# S7G7_footprint_simplified_w_ethernet_v1p.net
KiCad netlist of a schematic drawn in EAGLE
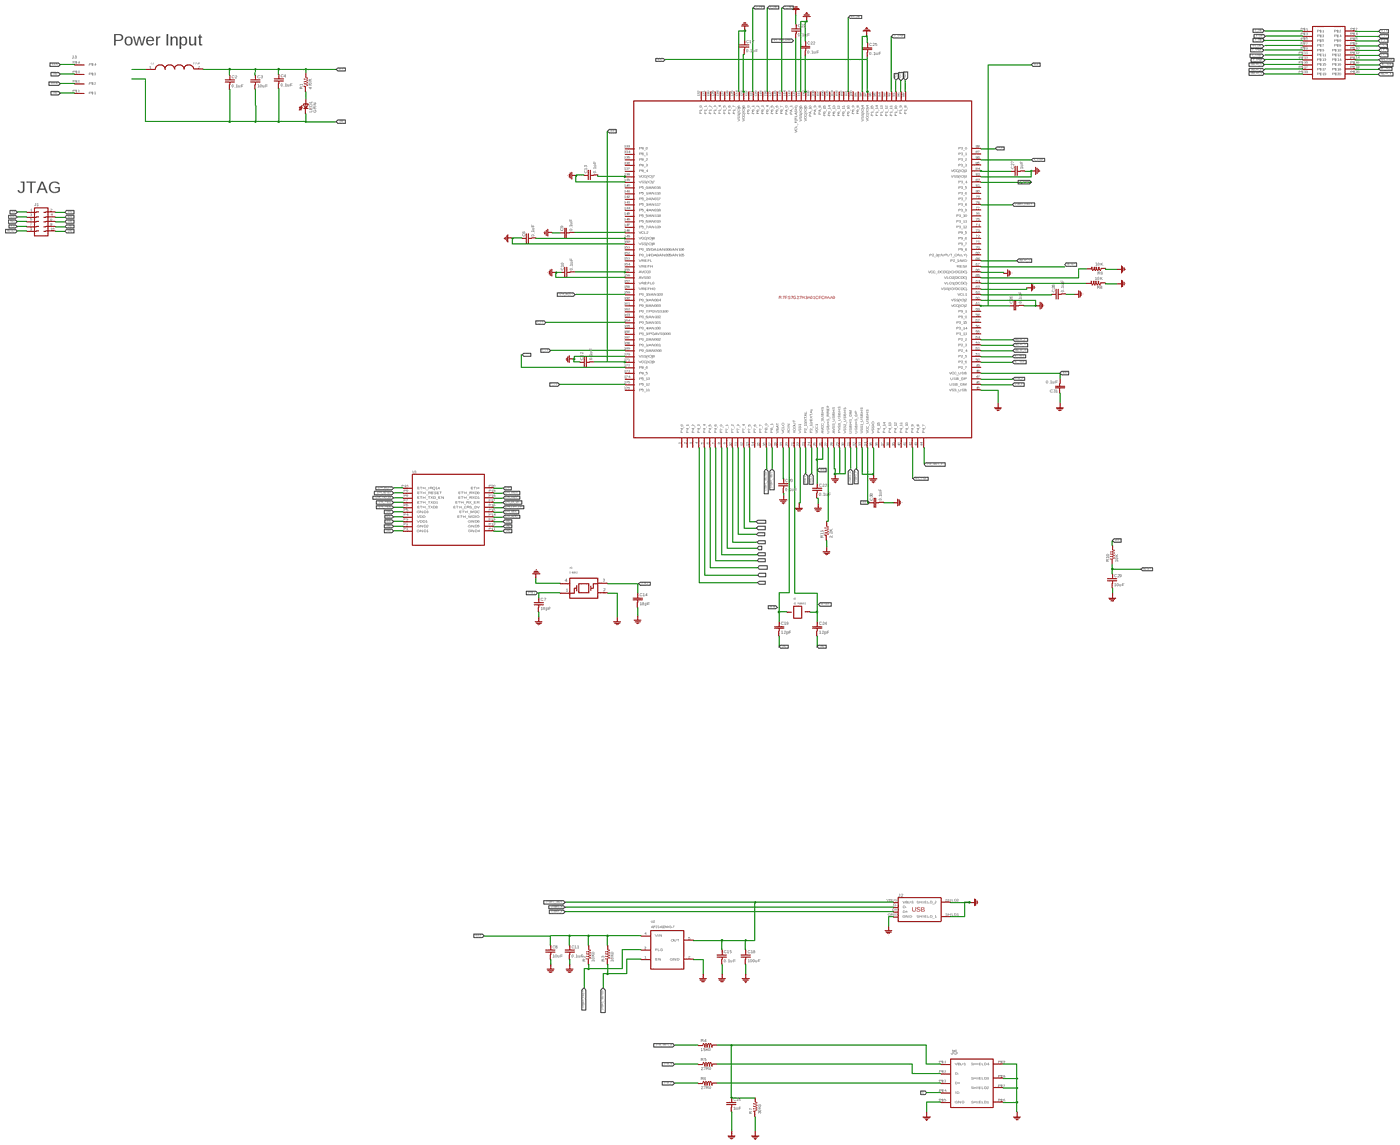
[diagram p0: schematic, sheet 1, overview]
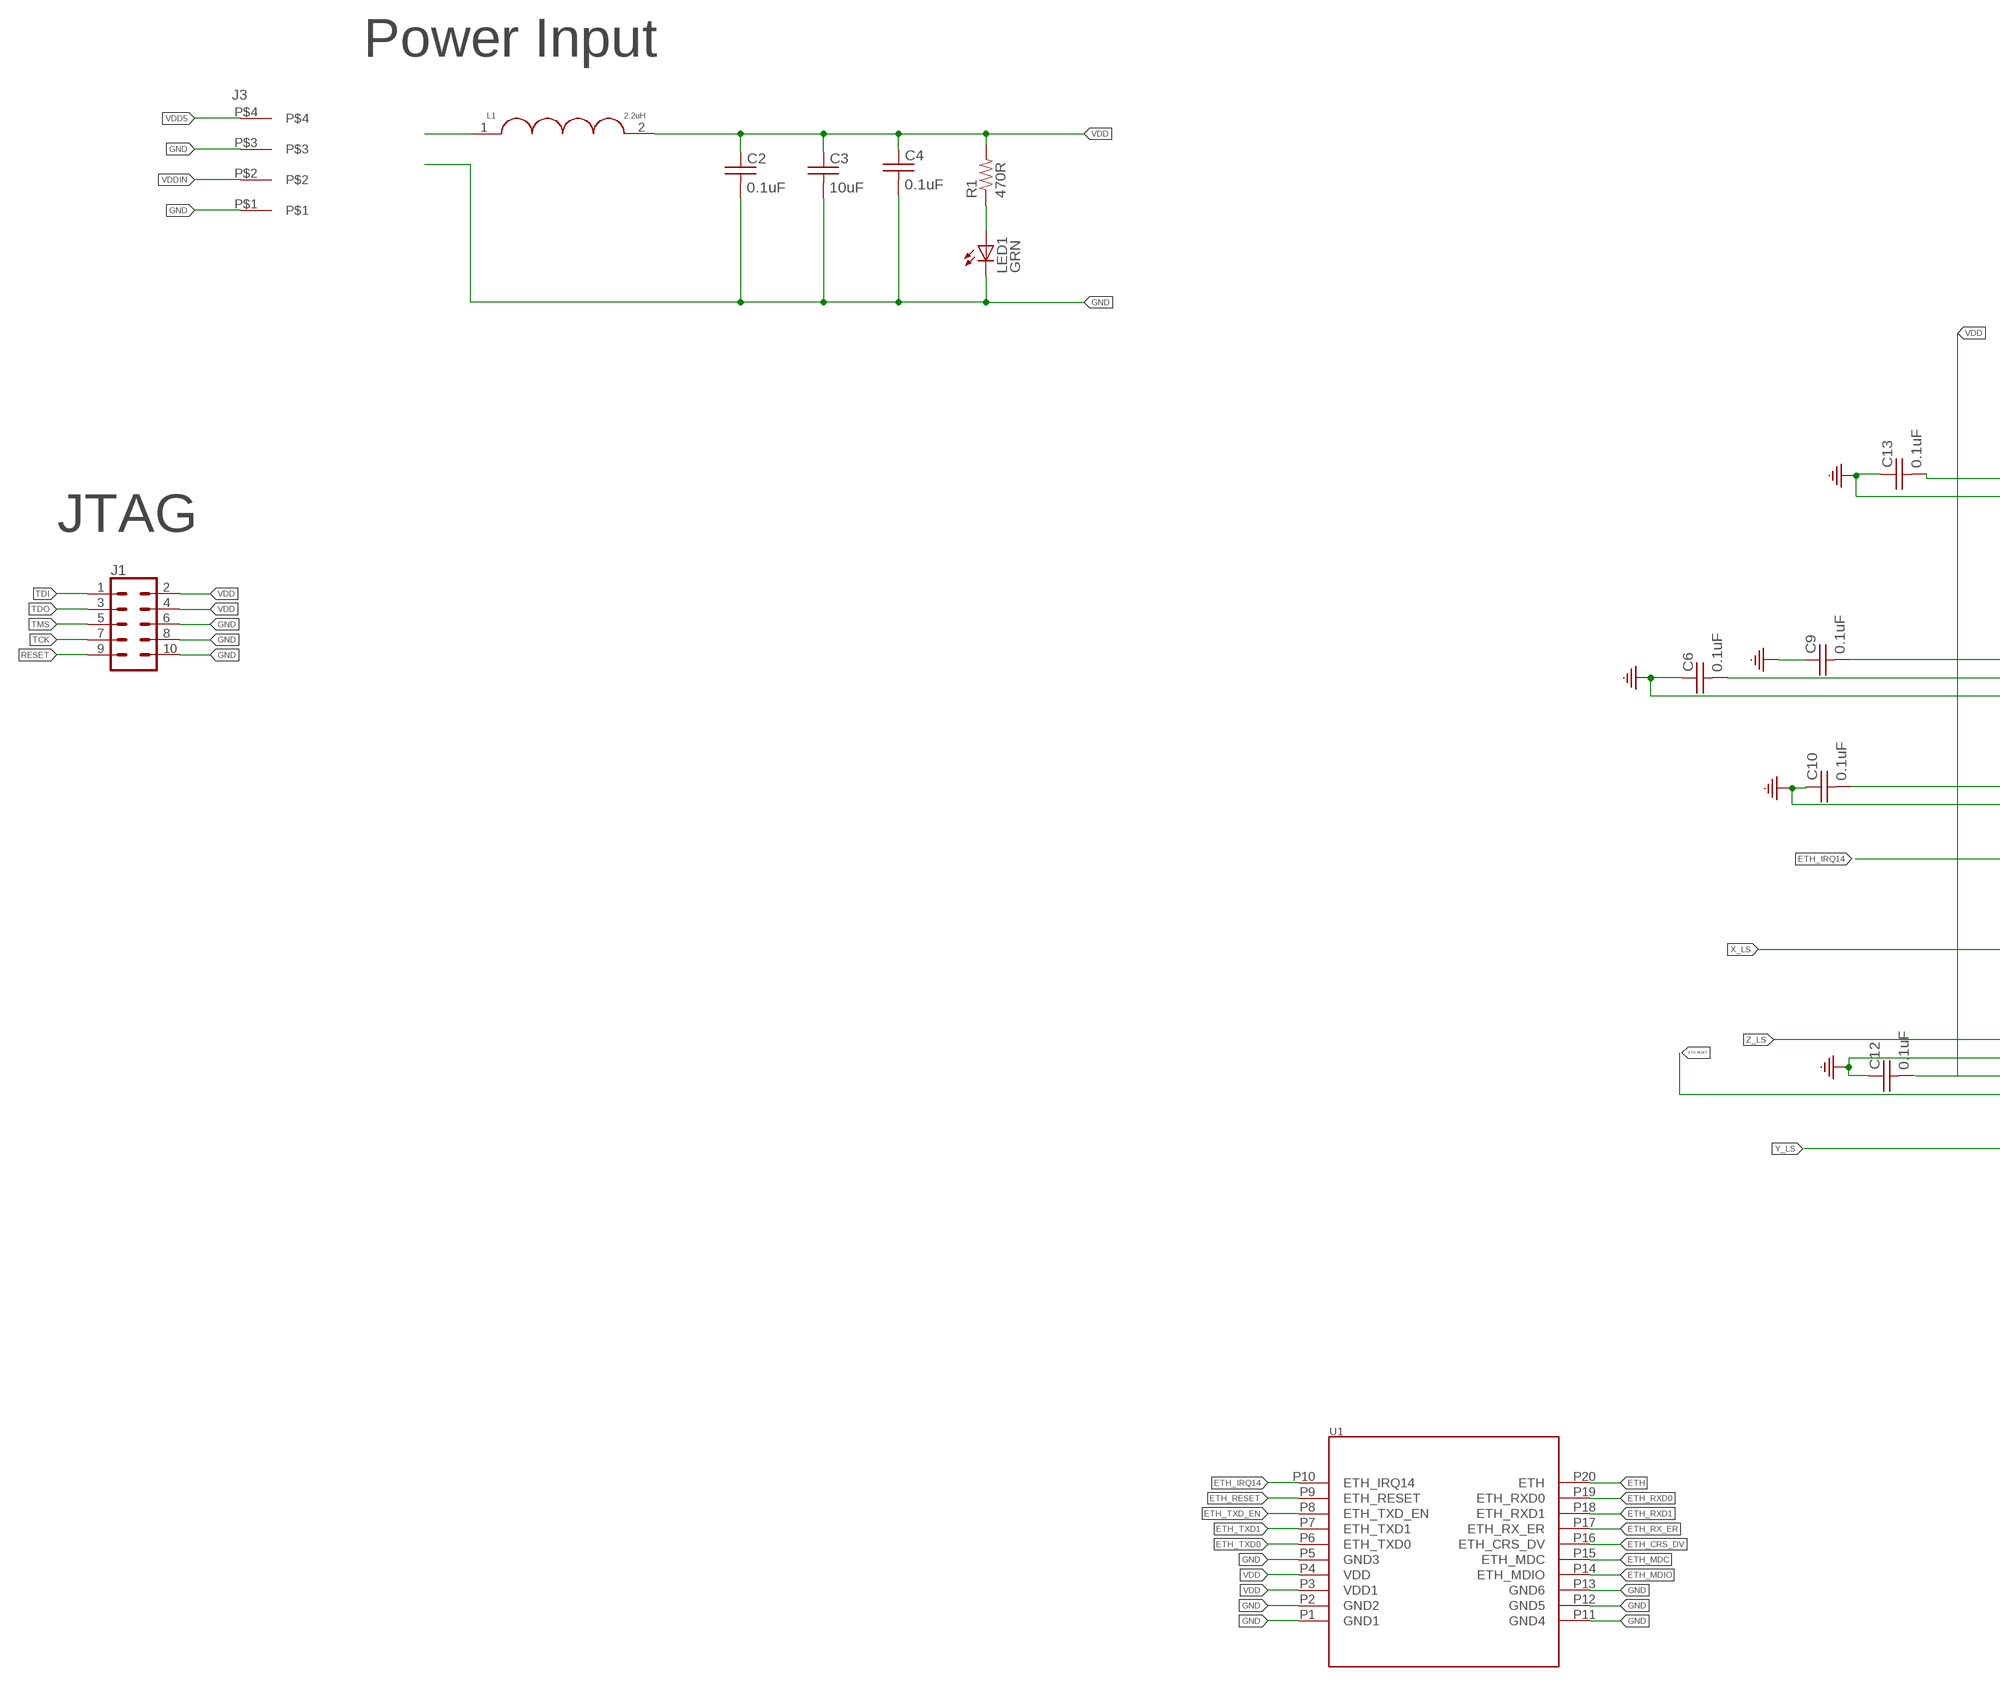
[diagram p1: schematic, sheet 1, part 1 of 4]
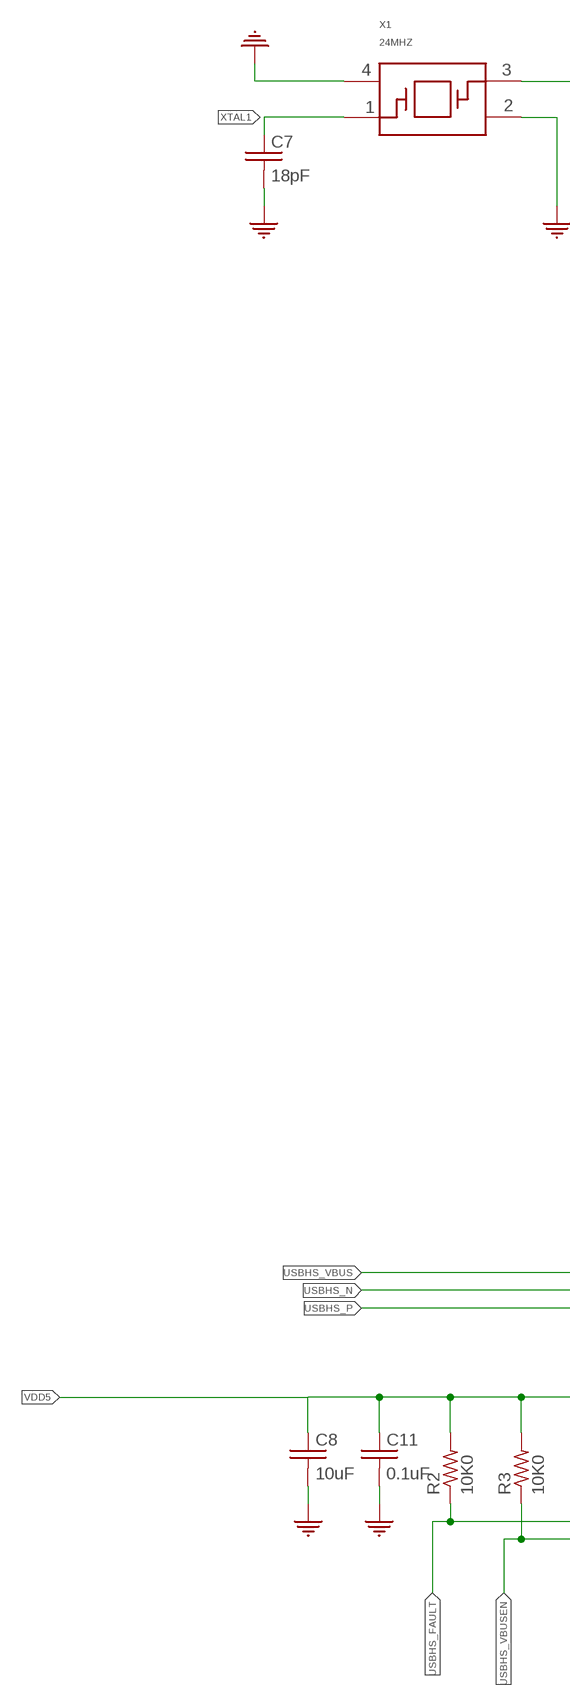
[diagram p2: schematic, sheet 1, part 2 of 4]
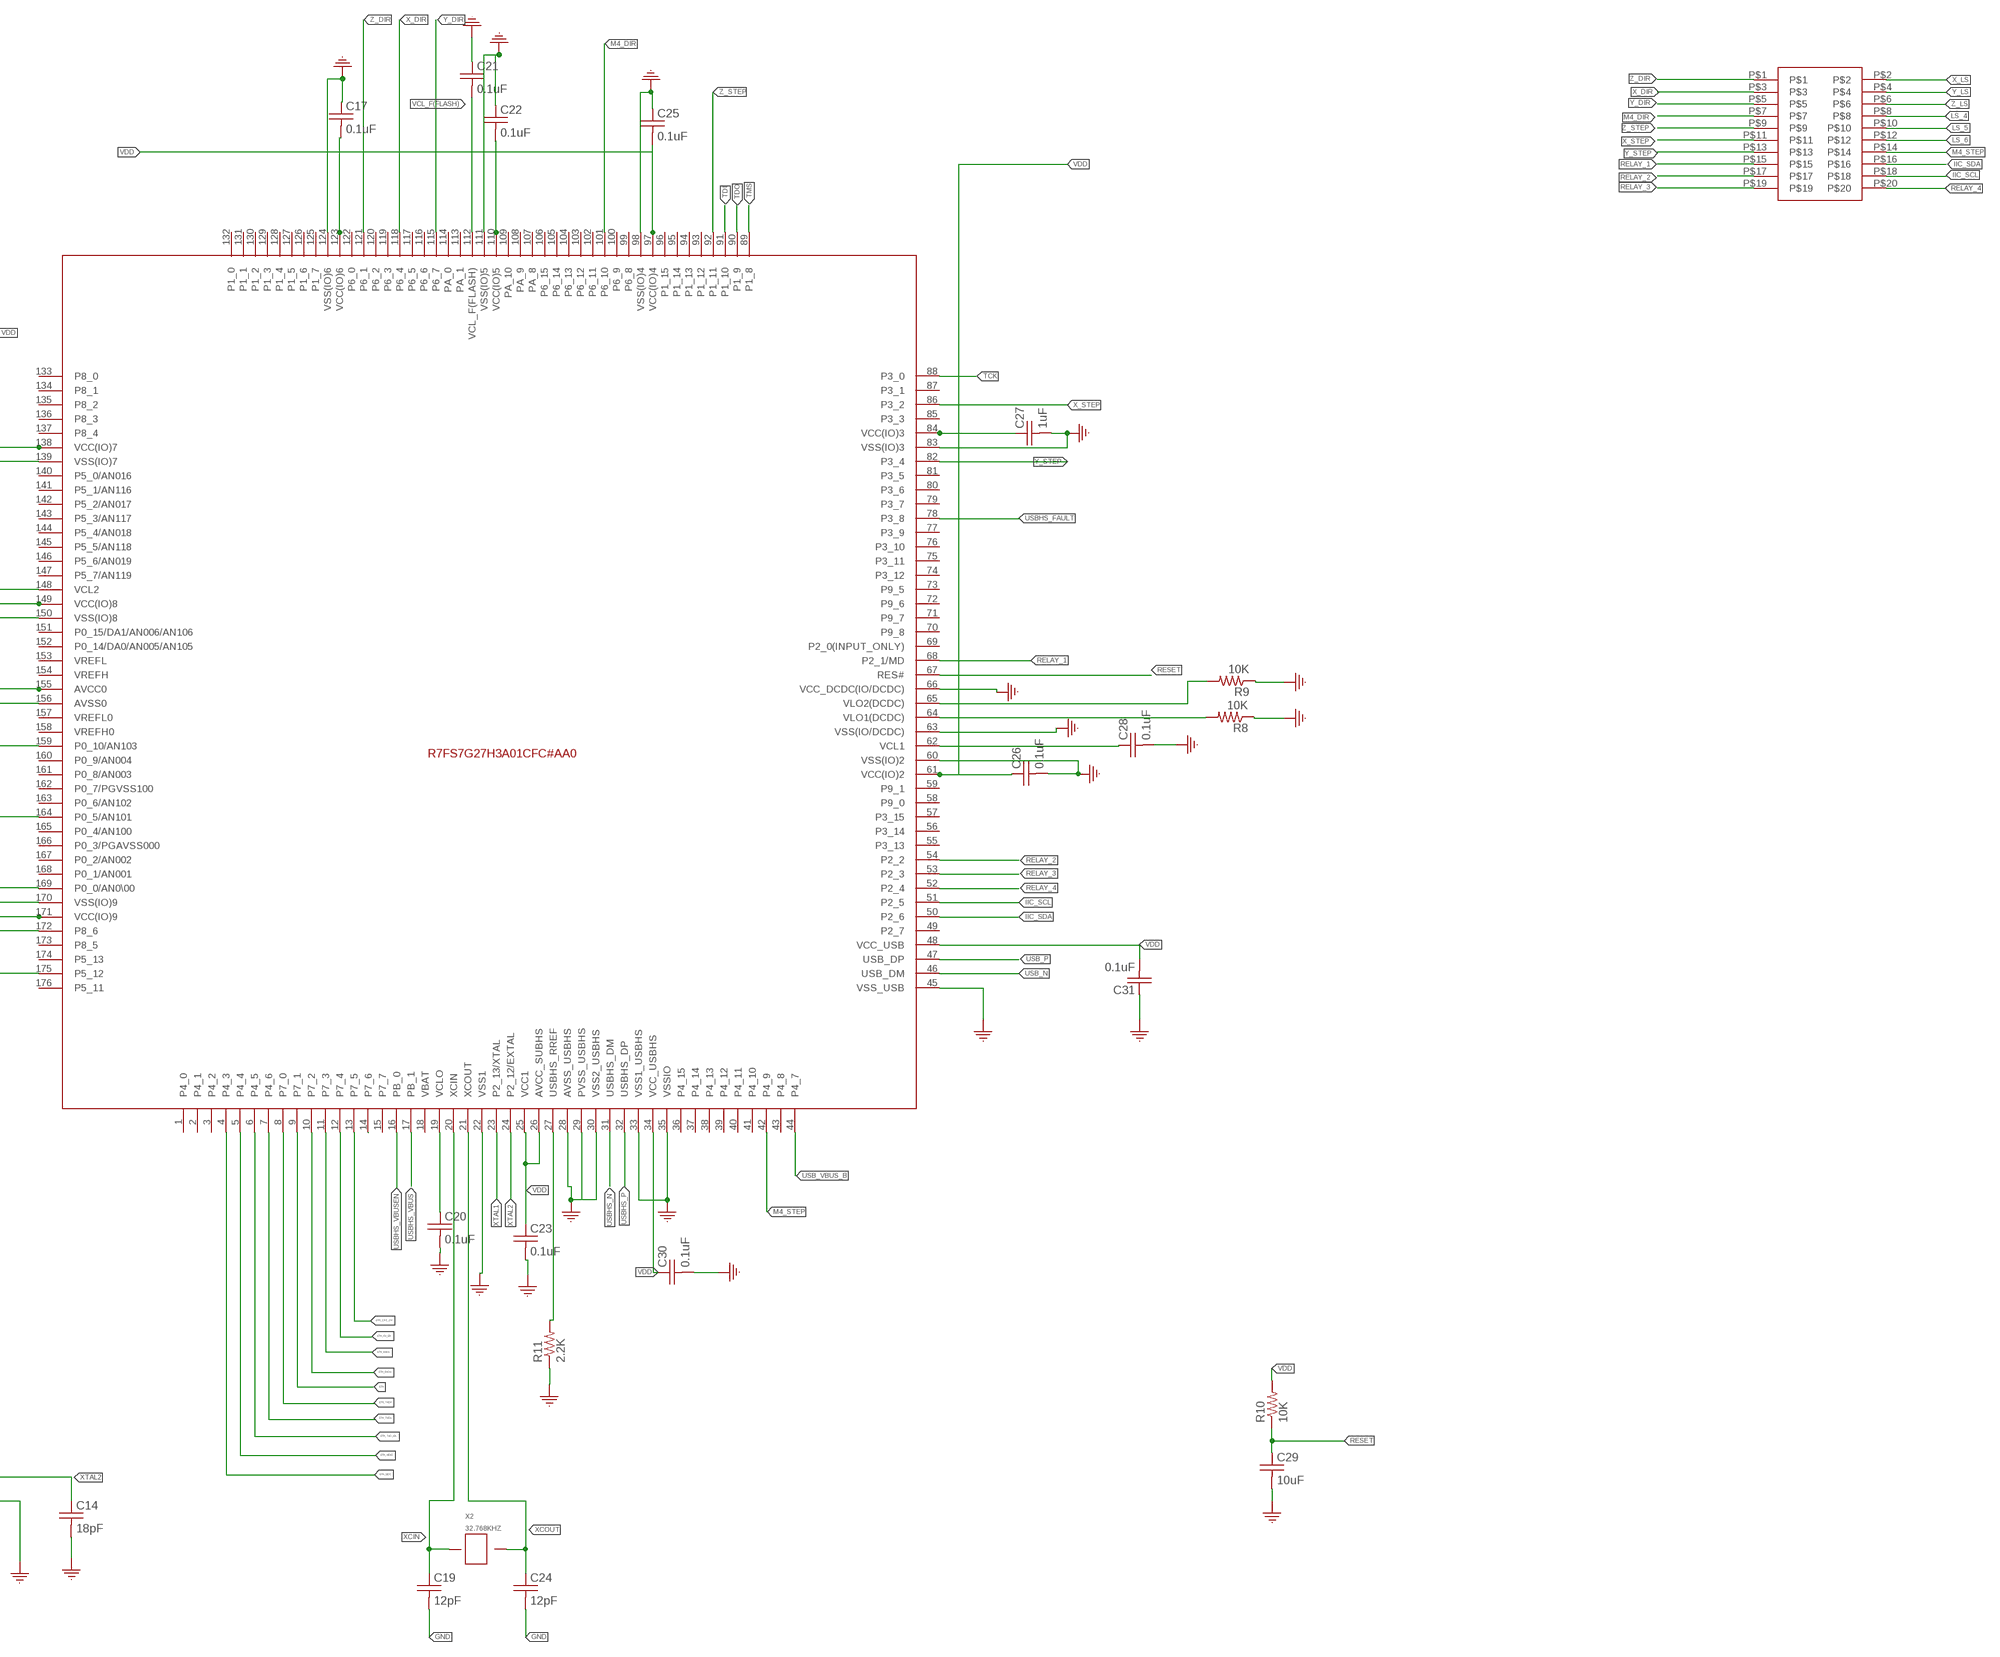
[diagram p3: schematic, sheet 1, part 3 of 4]
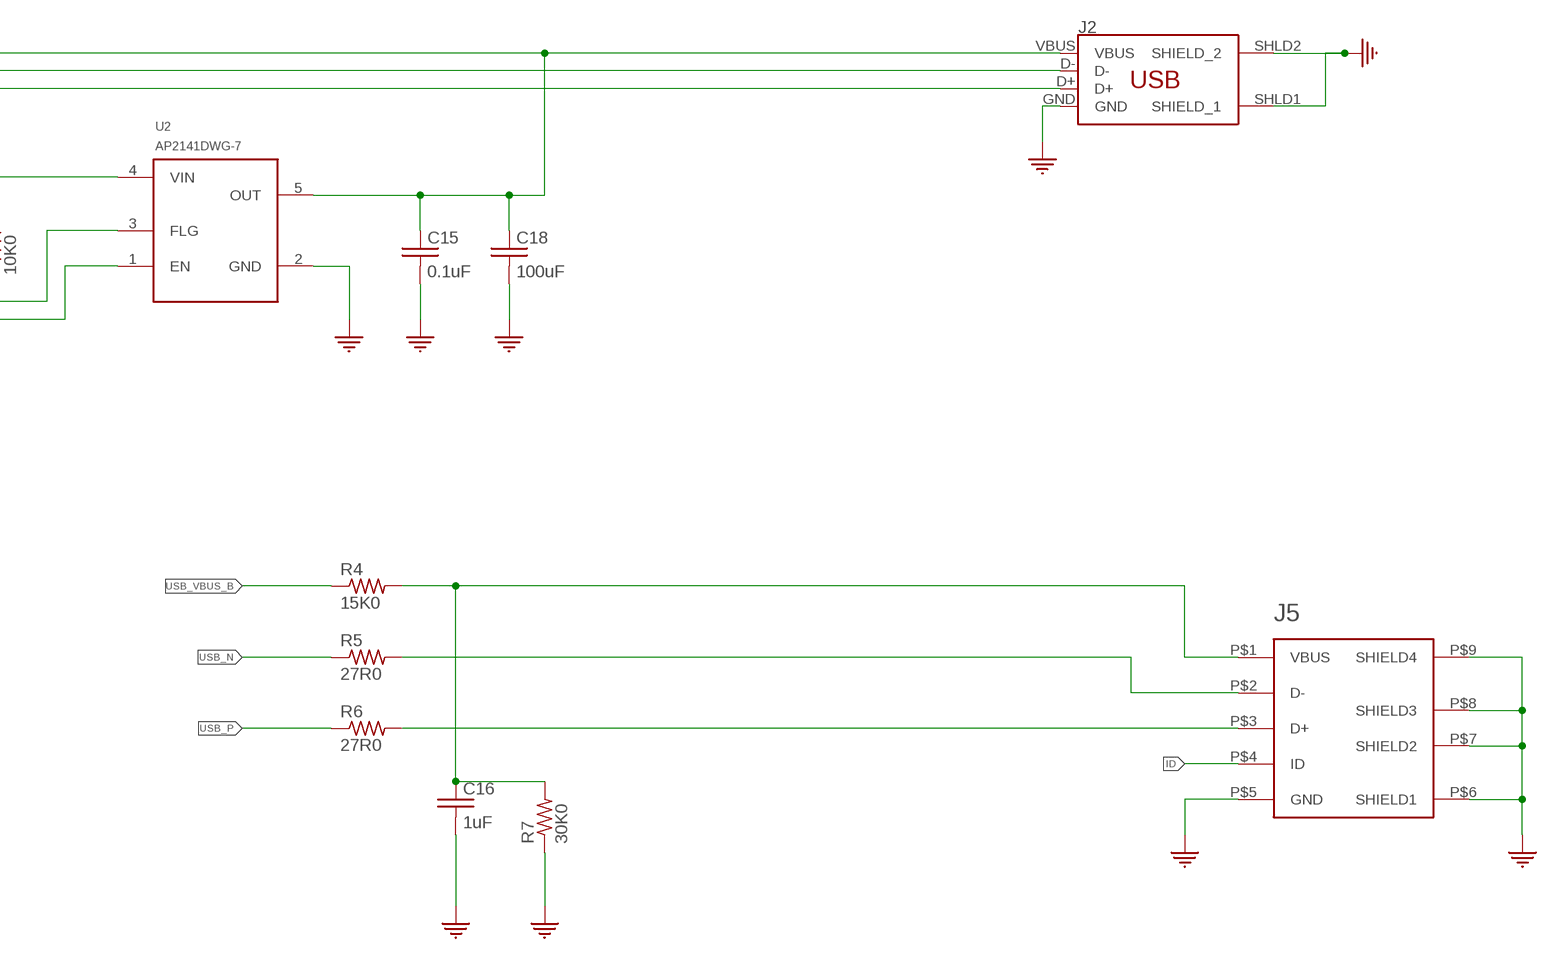
[diagram p4: schematic, sheet 1, part 4 of 4]

(export (version "E")
  (design (tool "Eeschema 10.0.6"))
  (components
    (comp (ref "C2")
      (value "0.1uF")
      (footprint "eagle-import:0402")
      (libsource (lib "eagle-import") (part "C_0402"))
    )
    (comp (ref "C3")
      (value "10uF")
      (footprint "eagle-import:0402")
      (libsource (lib "eagle-import") (part "C_0402"))
    )
    (comp (ref "C4")
      (value "0.1uF")
      (footprint "eagle-import:0402")
      (libsource (lib "eagle-import") (part "C_0402"))
    )
    (comp (ref "C6")
      (value "0.1uF")
      (footprint "eagle-import:0402")
      (libsource (lib "eagle-import") (part "C_0402"))
    )
    (comp (ref "C7")
      (value "18pF")
      (footprint "eagle-import:0402")
      (libsource (lib "eagle-import") (part "C_0402"))
    )
    (comp (ref "C8")
      (value "10uF")
      (footprint "eagle-import:0402")
      (libsource (lib "eagle-import") (part "C_0402"))
    )
    (comp (ref "C9")
      (value "0.1uF")
      (footprint "eagle-import:0402")
      (libsource (lib "eagle-import") (part "C_0402"))
    )
    (comp (ref "C10")
      (value "0.1uF")
      (footprint "eagle-import:0402")
      (libsource (lib "eagle-import") (part "C_0402"))
    )
    (comp (ref "C11")
      (value "0.1uF")
      (footprint "eagle-import:0402")
      (libsource (lib "eagle-import") (part "C_0402"))
    )
    (comp (ref "C12")
      (value "0.1uF")
      (footprint "eagle-import:0402")
      (libsource (lib "eagle-import") (part "C_0402"))
    )
    (comp (ref "C13")
      (value "0.1uF")
      (footprint "eagle-import:0402")
      (libsource (lib "eagle-import") (part "C_0402"))
    )
    (comp (ref "C14")
      (value "18pF")
      (footprint "eagle-import:0402")
      (libsource (lib "eagle-import") (part "C_0402"))
    )
    (comp (ref "C15")
      (value "0.1uF")
      (footprint "eagle-import:0402")
      (libsource (lib "eagle-import") (part "C_0402"))
    )
    (comp (ref "C16")
      (value "1uF")
      (footprint "eagle-import:0402")
      (libsource (lib "eagle-import") (part "C_0402"))
    )
    (comp (ref "C17")
      (value "0.1uF")
      (footprint "eagle-import:0402")
      (libsource (lib "eagle-import") (part "C_0402"))
    )
    (comp (ref "C18")
      (value "100uF")
      (footprint "eagle-import:C1210")
      (libsource (lib "eagle-import") (part "C_1210"))
    )
    (comp (ref "C19")
      (value "12pF")
      (footprint "eagle-import:0402")
      (libsource (lib "eagle-import") (part "C_0402"))
    )
    (comp (ref "C20")
      (value "0.1uF")
      (footprint "eagle-import:0402")
      (libsource (lib "eagle-import") (part "C_0402"))
    )
    (comp (ref "C21")
      (value "0.1uF")
      (footprint "eagle-import:0402")
      (libsource (lib "eagle-import") (part "C_0402"))
    )
    (comp (ref "C22")
      (value "0.1uF")
      (footprint "eagle-import:0402")
      (libsource (lib "eagle-import") (part "C_0402"))
    )
    (comp (ref "C23")
      (value "0.1uF")
      (footprint "eagle-import:0402")
      (libsource (lib "eagle-import") (part "C_0402"))
    )
    (comp (ref "C24")
      (value "12pF")
      (footprint "eagle-import:0402")
      (libsource (lib "eagle-import") (part "C_0402"))
    )
    (comp (ref "C25")
      (value "0.1uF")
      (footprint "eagle-import:0402")
      (libsource (lib "eagle-import") (part "C_0402"))
    )
    (comp (ref "C26")
      (value "0.1uF")
      (footprint "eagle-import:0402")
      (libsource (lib "eagle-import") (part "C_0402"))
    )
    (comp (ref "C27")
      (value "1uF")
      (footprint "eagle-import:0402")
      (libsource (lib "eagle-import") (part "C_0402"))
    )
    (comp (ref "C28")
      (value "0.1uF")
      (footprint "eagle-import:0402")
      (libsource (lib "eagle-import") (part "C_0402"))
    )
    (comp (ref "C29")
      (value "10uF")
      (footprint "eagle-import:0402")
      (libsource (lib "eagle-import") (part "C_0402"))
    )
    (comp (ref "C30")
      (value "0.1uF")
      (footprint "eagle-import:0402")
      (libsource (lib "eagle-import") (part "C_0402"))
    )
    (comp (ref "C31")
      (value "0.1uF")
      (footprint "eagle-import:0402")
      (libsource (lib "eagle-import") (part "C_0402"))
    )
    (comp (ref "J1")
      (value "CONN_05X2PTH")
      (footprint "eagle-import:2X5")
      (libsource (lib "eagle-import") (part "CONN_05X2PTH"))
    )
    (comp (ref "J2")
      (value "USB_A")
      (footprint "eagle-import:USB_A_SMT")
      (libsource (lib "eagle-import") (part "USB_A"))
    )
    (comp (ref "J3")
      (value "3.81MM_1_X_4_RT_ANGLE_PLUG_HEADER")
      (footprint "eagle-import:1X4_3.81MM_PITCH")
      (libsource (lib "eagle-import") (part "3.81MM_1_X_4_RT_ANGLE_PLUG_HEADER"))
    )
    (comp (ref "J4")
      (value "2_X_10_HEADER_GENERIC")
      (footprint "eagle-import:2_X_10_.1_INCH")
      (libsource (lib "eagle-import") (part "2_X_10_HEADER_GENERIC"))
    )
    (comp (ref "J5")
      (value "USB_MICRO-B")
      (footprint "eagle-import:USB_MICRO-B")
      (libsource (lib "eagle-import") (part "USB_MICRO-B"))
    )
    (comp (ref "L1")
      (value "2.2uH")
      (footprint "eagle-import:1008_(2520_METRIC)")
      (libsource (lib "eagle-import") (part "INDUCTOR_1008_2.2_MH_1.3A"))
    )
    (comp (ref "LED1")
      (value "LED_0805_GREEN")
      (footprint "eagle-import:LED_0805_GREEN")
      (libsource (lib "eagle-import") (part "LED_0805_GREEN"))
    )
    (comp (ref "R1")
      (value "470R")
      (footprint "eagle-import:0402")
      (libsource (lib "eagle-import") (part "R_0402"))
    )
    (comp (ref "R2")
      (value "10K0")
      (footprint "eagle-import:0402")
      (libsource (lib "eagle-import") (part "R_0402"))
    )
    (comp (ref "R3")
      (value "10K0")
      (footprint "eagle-import:0402")
      (libsource (lib "eagle-import") (part "R_0402"))
    )
    (comp (ref "R4")
      (value "15K0")
      (footprint "eagle-import:0402")
      (libsource (lib "eagle-import") (part "R_0402"))
    )
    (comp (ref "R5")
      (value "27R0")
      (footprint "eagle-import:0402")
      (libsource (lib "eagle-import") (part "R_0402"))
    )
    (comp (ref "R6")
      (value "27R0")
      (footprint "eagle-import:0402")
      (libsource (lib "eagle-import") (part "R_0402"))
    )
    (comp (ref "R7")
      (value "30K0")
      (footprint "eagle-import:0402")
      (libsource (lib "eagle-import") (part "R_0402"))
    )
    (comp (ref "R8")
      (value "10K")
      (footprint "eagle-import:0402")
      (libsource (lib "eagle-import") (part "R_0402"))
    )
    (comp (ref "R9")
      (value "10K")
      (footprint "eagle-import:0402")
      (libsource (lib "eagle-import") (part "R_0402"))
    )
    (comp (ref "R10")
      (value "10K")
      (footprint "eagle-import:0402")
      (libsource (lib "eagle-import") (part "R_0402"))
    )
    (comp (ref "R11")
      (value "2.2K")
      (footprint "eagle-import:0402")
      (libsource (lib "eagle-import") (part "R_0402"))
    )
    (comp (ref "U1")
      (value "ETHERNET_HAT")
      (footprint "eagle-import:ETHERNET_HAT")
      (libsource (lib "eagle-import") (part "ETHERNET_HAT"))
    )
    (comp (ref "U2")
      (value "AP2141DWG-5")
      (footprint "eagle-import:SOT-23-5")
      (libsource (lib "eagle-import") (part "AP2141DWG-5"))
    )
    (comp (ref "U5")
      (value "S7G2_X_176")
      (footprint "eagle-import:LQFP176_24X24")
      (libsource (lib "eagle-import") (part "S7G2_X_176"))
    )
    (comp (ref "X1")
      (value "24MHZ")
      (footprint "eagle-import:SMD_3225")
      (libsource (lib "eagle-import") (part "XTAL_24_MHZ"))
    )
    (comp (ref "X2")
      (value "32.768KHZ")
      (footprint "eagle-import:SMD_X_2_PADS")
      (libsource (lib "eagle-import") (part "XTAL_32.768KHZ"))
    )
  )
  (nets
    (net (code "1") (name "ETH") (class "Default")
      (node (ref "U1") (pin "P20") (pinfunction "ETH_P20") (pintype "bidirectional"))
      (node (ref "U5") (pin "9") (pinfunction "P7_1_9") (pintype "bidirectional"))
    )
    (net (code "2") (name "ETH_CRS_DV") (class "Default")
      (node (ref "U1") (pin "P16") (pinfunction "ETH_CRS_DV_P16") (pintype "bidirectional"))
      (node (ref "U5") (pin "13") (pinfunction "P7_5_13") (pintype "bidirectional"))
    )
    (net (code "3") (name "ETH_IRQ14") (class "Default")
      (node (ref "U1") (pin "P10") (pinfunction "ETH_IRQ14_P10") (pintype "bidirectional"))
      (node (ref "U5") (pin "159") (pinfunction "P0_10/AN103_159") (pintype "bidirectional"))
    )
    (net (code "4") (name "ETH_MDC") (class "Default")
      (node (ref "U1") (pin "P15") (pinfunction "ETH_MDC_P15") (pintype "bidirectional"))
      (node (ref "U5") (pin "4") (pinfunction "P4_3_4") (pintype "bidirectional"))
    )
    (net (code "5") (name "ETH_MDIO") (class "Default")
      (node (ref "U1") (pin "P14") (pinfunction "ETH_MDIO_P14") (pintype "bidirectional"))
      (node (ref "U5") (pin "5") (pinfunction "P4_4_5") (pintype "bidirectional"))
    )
    (net (code "6") (name "ETH_RESET") (class "Default")
      (node (ref "U1") (pin "P9") (pinfunction "ETH_RESET_P9") (pintype "bidirectional"))
      (node (ref "U5") (pin "172") (pinfunction "P8_6_172") (pintype "bidirectional"))
    )
    (net (code "7") (name "ETH_RXD0") (class "Default")
      (node (ref "U1") (pin "P19") (pinfunction "ETH_RXD0_P19") (pintype "bidirectional"))
      (node (ref "U5") (pin "10") (pinfunction "P7_2_10") (pintype "bidirectional"))
    )
    (net (code "8") (name "ETH_RXD1") (class "Default")
      (node (ref "U1") (pin "P18") (pinfunction "ETH_RXD1_P18") (pintype "bidirectional"))
      (node (ref "U5") (pin "11") (pinfunction "P7_3_11") (pintype "bidirectional"))
    )
    (net (code "9") (name "ETH_RX_ER") (class "Default")
      (node (ref "U1") (pin "P17") (pinfunction "ETH_RX_ER_P17") (pintype "bidirectional"))
      (node (ref "U5") (pin "12") (pinfunction "P7_4_12") (pintype "bidirectional"))
    )
    (net (code "10") (name "ETH_TXD0") (class "Default")
      (node (ref "U1") (pin "P6") (pinfunction "ETH_TXD0_P6") (pintype "bidirectional"))
      (node (ref "U5") (pin "8") (pinfunction "P7_0_8") (pintype "bidirectional"))
    )
    (net (code "11") (name "ETH_TXD1") (class "Default")
      (node (ref "U1") (pin "P7") (pinfunction "ETH_TXD1_P7") (pintype "bidirectional"))
      (node (ref "U5") (pin "7") (pinfunction "P4_6_7") (pintype "bidirectional"))
    )
    (net (code "12") (name "ETH_TXD_EN") (class "Default")
      (node (ref "U1") (pin "P8") (pinfunction "ETH_TXD_EN_P8") (pintype "bidirectional"))
      (node (ref "U5") (pin "6") (pinfunction "P4_5_6") (pintype "bidirectional"))
    )
    (net (code "13") (name "GND") (class "Default")
      (node (ref "C10") (pin "P$1") (pinfunction "1_P$1") (pintype "passive"))
      (node (ref "C11") (pin "P$2") (pinfunction "2_P$2") (pintype "passive"))
      (node (ref "C12") (pin "P$1") (pinfunction "1_P$1") (pintype "passive"))
      (node (ref "C13") (pin "P$1") (pinfunction "1_P$1") (pintype "passive"))
      (node (ref "C14") (pin "P$2") (pinfunction "2_P$2") (pintype "passive"))
      (node (ref "C15") (pin "P$2") (pinfunction "2_P$2") (pintype "passive"))
      (node (ref "C16") (pin "P$2") (pinfunction "2_P$2") (pintype "passive"))
      (node (ref "C17") (pin "P$1") (pinfunction "1_P$1") (pintype "passive"))
      (node (ref "C18") (pin "2") (pinfunction "2_2") (pintype "passive"))
      (node (ref "C19") (pin "P$2") (pinfunction "2_P$2") (pintype "passive"))
      (node (ref "C2") (pin "P$2") (pinfunction "2_P$2") (pintype "passive"))
      (node (ref "C20") (pin "P$2") (pinfunction "2_P$2") (pintype "passive"))
      (node (ref "C21") (pin "P$1") (pinfunction "1_P$1") (pintype "passive"))
      (node (ref "C22") (pin "P$1") (pinfunction "1_P$1") (pintype "passive"))
      (node (ref "C23") (pin "P$2") (pinfunction "2_P$2") (pintype "passive"))
      (node (ref "C24") (pin "P$2") (pinfunction "2_P$2") (pintype "passive"))
      (node (ref "C25") (pin "P$1") (pinfunction "1_P$1") (pintype "passive"))
      (node (ref "C26") (pin "P$2") (pinfunction "2_P$2") (pintype "passive"))
      (node (ref "C27") (pin "P$2") (pinfunction "2_P$2") (pintype "passive"))
      (node (ref "C28") (pin "P$2") (pinfunction "2_P$2") (pintype "passive"))
      (node (ref "C29") (pin "P$2") (pinfunction "2_P$2") (pintype "passive"))
      (node (ref "C3") (pin "P$2") (pinfunction "2_P$2") (pintype "passive"))
      (node (ref "C30") (pin "P$2") (pinfunction "2_P$2") (pintype "passive"))
      (node (ref "C31") (pin "P$1") (pinfunction "1_P$1") (pintype "passive"))
      (node (ref "C4") (pin "P$2") (pinfunction "2_P$2") (pintype "passive"))
      (node (ref "C6") (pin "P$1") (pinfunction "1_P$1") (pintype "passive"))
      (node (ref "C7") (pin "P$2") (pinfunction "2_P$2") (pintype "passive"))
      (node (ref "C8") (pin "P$2") (pinfunction "2_P$2") (pintype "passive"))
      (node (ref "C9") (pin "P$1") (pinfunction "1_P$1") (pintype "passive"))
      (node (ref "J1") (pin "10") (pinfunction "10_10") (pintype "passive"))
      (node (ref "J1") (pin "6") (pinfunction "6_6") (pintype "passive"))
      (node (ref "J1") (pin "8") (pinfunction "8_8") (pintype "passive"))
      (node (ref "J2") (pin "GND") (pinfunction "GND_GND") (pintype "power_in"))
      (node (ref "J2") (pin "SHLD1") (pinfunction "SHIELD_1_SHLD1") (pintype "bidirectional"))
      (node (ref "J2") (pin "SHLD2") (pinfunction "SHIELD_2_SHLD2") (pintype "bidirectional"))
      (node (ref "J3") (pin "P$1") (pinfunction "P$1_P$1") (pintype "bidirectional"))
      (node (ref "J3") (pin "P$3") (pinfunction "P$3_P$3") (pintype "bidirectional"))
      (node (ref "J5") (pin "P$5") (pinfunction "GND_P$5") (pintype "bidirectional"))
      (node (ref "J5") (pin "P$6") (pinfunction "SHIELD1_P$6") (pintype "bidirectional"))
      (node (ref "J5") (pin "P$7") (pinfunction "SHIELD2_P$7") (pintype "bidirectional"))
      (node (ref "J5") (pin "P$8") (pinfunction "SHIELD3_P$8") (pintype "bidirectional"))
      (node (ref "J5") (pin "P$9") (pinfunction "SHIELD4_P$9") (pintype "bidirectional"))
      (node (ref "LED1") (pin "C") (pinfunction "C_C") (pintype "passive"))
      (node (ref "R11") (pin "P$1") (pinfunction "1_P$1") (pintype "passive"))
      (node (ref "R7") (pin "P$1") (pinfunction "1_P$1") (pintype "passive"))
      (node (ref "R8") (pin "P$1") (pinfunction "1_P$1") (pintype "passive"))
      (node (ref "R9") (pin "P$1") (pinfunction "1_P$1") (pintype "passive"))
      (node (ref "U1") (pin "P1") (pinfunction "GND1_P1") (pintype "bidirectional"))
      (node (ref "U1") (pin "P11") (pinfunction "GND4_P11") (pintype "bidirectional"))
      (node (ref "U1") (pin "P12") (pinfunction "GND5_P12") (pintype "bidirectional"))
      (node (ref "U1") (pin "P13") (pinfunction "GND6_P13") (pintype "bidirectional"))
      (node (ref "U1") (pin "P2") (pinfunction "GND2_P2") (pintype "bidirectional"))
      (node (ref "U1") (pin "P5") (pinfunction "GND3_P5") (pintype "bidirectional"))
      (node (ref "U2") (pin "2") (pinfunction "GND_2") (pintype "input"))
      (node (ref "U5") (pin "111") (pinfunction "VSS(IO)5_111") (pintype "bidirectional"))
      (node (ref "U5") (pin "124") (pinfunction "VSS(IO)6_124") (pintype "bidirectional"))
      (node (ref "U5") (pin "139") (pinfunction "VSS(IO)7_139") (pintype "bidirectional"))
      (node (ref "U5") (pin "150") (pinfunction "VSS(IO)8_150") (pintype "bidirectional"))
      (node (ref "U5") (pin "156") (pinfunction "AVSS0_156") (pintype "bidirectional"))
      (node (ref "U5") (pin "170") (pinfunction "VSS(IO)9_170") (pintype "bidirectional"))
      (node (ref "U5") (pin "22") (pinfunction "VSS1_22") (pintype "bidirectional"))
      (node (ref "U5") (pin "28") (pinfunction "AVSS_USBHS_28") (pintype "bidirectional"))
      (node (ref "U5") (pin "29") (pinfunction "PVSS_USBHS_29") (pintype "bidirectional"))
      (node (ref "U5") (pin "30") (pinfunction "VSS2_USBHS_30") (pintype "bidirectional"))
      (node (ref "U5") (pin "33") (pinfunction "VSS1_USBHS_33") (pintype "bidirectional"))
      (node (ref "U5") (pin "35") (pinfunction "VSSIO_35") (pintype "bidirectional"))
      (node (ref "U5") (pin "45") (pinfunction "VSS_USB_45") (pintype "bidirectional"))
      (node (ref "U5") (pin "60") (pinfunction "VSS(IO)2_60") (pintype "bidirectional"))
      (node (ref "U5") (pin "63") (pinfunction "VSS(IO/DCDC)_63") (pintype "bidirectional"))
      (node (ref "U5") (pin "66") (pinfunction "VCC_DCDC(IO/DCDC)_66") (pintype "bidirectional"))
      (node (ref "U5") (pin "83") (pinfunction "VSS(IO)3_83") (pintype "bidirectional"))
      (node (ref "U5") (pin "98") (pinfunction "VSS(IO)4_98") (pintype "bidirectional"))
      (node (ref "X1") (pin "2") (pinfunction "2_2") (pintype "bidirectional"))
      (node (ref "X1") (pin "4") (pinfunction "4_4") (pintype "bidirectional"))
    )
    (net (code "14") (name "ID") (class "Default")
      (node (ref "J5") (pin "P$4") (pinfunction "ID_P$4") (pintype "bidirectional"))
    )
    (net (code "15") (name "IIC_SCL") (class "Default")
      (node (ref "J4") (pin "P$18") (pinfunction "P$18_P$18") (pintype "bidirectional"))
      (node (ref "U5") (pin "51") (pinfunction "P2_5_51") (pintype "bidirectional"))
    )
    (net (code "16") (name "IIC_SDA") (class "Default")
      (node (ref "J4") (pin "P$16") (pinfunction "P$16_P$16") (pintype "bidirectional"))
      (node (ref "U5") (pin "50") (pinfunction "P2_6_50") (pintype "bidirectional"))
    )
    (net (code "17") (name "LS_4") (class "Default")
      (node (ref "J4") (pin "P$8") (pinfunction "P$8_P$8") (pintype "bidirectional"))
    )
    (net (code "18") (name "LS_5") (class "Default")
      (node (ref "J4") (pin "P$10") (pinfunction "P$10_P$10") (pintype "bidirectional"))
    )
    (net (code "19") (name "LS_6") (class "Default")
      (node (ref "J4") (pin "P$12") (pinfunction "P$12_P$12") (pintype "bidirectional"))
    )
    (net (code "20") (name "M4_DIR") (class "Default")
      (node (ref "J4") (pin "P$7") (pinfunction "P$7_P$7") (pintype "bidirectional"))
      (node (ref "U5") (pin "101") (pinfunction "P6_10_101") (pintype "bidirectional"))
    )
    (net (code "21") (name "M4_STEP") (class "Default")
      (node (ref "J4") (pin "P$14") (pinfunction "P$14_P$14") (pintype "bidirectional"))
      (node (ref "U5") (pin "42") (pinfunction "P4_9_42") (pintype "bidirectional"))
    )
    (net (code "22") (name "Net-(C9-2)") (class "Default")
      (node (ref "C9") (pin "P$2") (pinfunction "2_P$2") (pintype "passive"))
      (node (ref "U5") (pin "148") (pinfunction "VCL2_148") (pintype "bidirectional"))
    )
    (net (code "23") (name "Net-(C16-1)") (class "Default")
      (node (ref "C16") (pin "P$1") (pinfunction "1_P$1") (pintype "passive"))
      (node (ref "J5") (pin "P$1") (pinfunction "VBUS_P$1") (pintype "bidirectional"))
      (node (ref "R4") (pin "P$2") (pinfunction "2_P$2") (pintype "passive"))
      (node (ref "R7") (pin "P$2") (pinfunction "2_P$2") (pintype "passive"))
    )
    (net (code "24") (name "Net-(C20-1)") (class "Default")
      (node (ref "C20") (pin "P$1") (pinfunction "1_P$1") (pintype "passive"))
      (node (ref "U5") (pin "19") (pinfunction "VCLO_19") (pintype "bidirectional"))
    )
    (net (code "25") (name "Net-(C28-1)") (class "Default")
      (node (ref "C28") (pin "P$1") (pinfunction "1_P$1") (pintype "passive"))
      (node (ref "U5") (pin "62") (pinfunction "VCL1_62") (pintype "bidirectional"))
    )
    (net (code "26") (name "Net-(J5-D+)") (class "Default")
      (node (ref "J5") (pin "P$3") (pinfunction "D+_P$3") (pintype "bidirectional"))
      (node (ref "R6") (pin "P$2") (pinfunction "2_P$2") (pintype "passive"))
    )
    (net (code "27") (name "Net-(J5-D-)") (class "Default")
      (node (ref "J5") (pin "P$2") (pinfunction "D-_P$2") (pintype "bidirectional"))
      (node (ref "R5") (pin "P$2") (pinfunction "2_P$2") (pintype "passive"))
    )
    (net (code "28") (name "Net-(R1-1)") (class "Default")
      (node (ref "LED1") (pin "A") (pinfunction "A_A") (pintype "passive"))
      (node (ref "R1") (pin "P$1") (pinfunction "1_P$1") (pintype "passive"))
    )
    (net (code "29") (name "Net-(R8-2)") (class "Default")
      (node (ref "R8") (pin "P$2") (pinfunction "2_P$2") (pintype "passive"))
      (node (ref "U5") (pin "64") (pinfunction "VLO1(DCDC)_64") (pintype "bidirectional"))
    )
    (net (code "30") (name "Net-(R9-2)") (class "Default")
      (node (ref "R9") (pin "P$2") (pinfunction "2_P$2") (pintype "passive"))
      (node (ref "U5") (pin "65") (pinfunction "VLO2(DCDC)_65") (pintype "bidirectional"))
    )
    (net (code "31") (name "Net-(R11-2)") (class "Default")
      (node (ref "R11") (pin "P$2") (pinfunction "2_P$2") (pintype "passive"))
      (node (ref "U5") (pin "27") (pinfunction "USBHS_RREF_27") (pintype "bidirectional"))
    )
    (net (code "32") (name "RELAY_1") (class "Default")
      (node (ref "J4") (pin "P$15") (pinfunction "P$15_P$15") (pintype "bidirectional"))
      (node (ref "U5") (pin "68") (pinfunction "P2_1/MD_68") (pintype "bidirectional"))
    )
    (net (code "33") (name "RELAY_2") (class "Default")
      (node (ref "J4") (pin "P$17") (pinfunction "P$17_P$17") (pintype "bidirectional"))
      (node (ref "U5") (pin "54") (pinfunction "P2_2_54") (pintype "bidirectional"))
    )
    (net (code "34") (name "RELAY_3") (class "Default")
      (node (ref "J4") (pin "P$19") (pinfunction "P$19_P$19") (pintype "bidirectional"))
      (node (ref "U5") (pin "53") (pinfunction "P2_3_53") (pintype "bidirectional"))
    )
    (net (code "35") (name "RELAY_4") (class "Default")
      (node (ref "J4") (pin "P$20") (pinfunction "P$20_P$20") (pintype "bidirectional"))
      (node (ref "U5") (pin "52") (pinfunction "P2_4_52") (pintype "bidirectional"))
    )
    (net (code "36") (name "RESET") (class "Default")
      (node (ref "C29") (pin "P$1") (pinfunction "1_P$1") (pintype "passive"))
      (node (ref "J1") (pin "9") (pinfunction "9_9") (pintype "passive"))
      (node (ref "R10") (pin "P$1") (pinfunction "1_P$1") (pintype "passive"))
      (node (ref "U5") (pin "67") (pinfunction "RES#_67") (pintype "bidirectional"))
    )
    (net (code "37") (name "TCK") (class "Default")
      (node (ref "J1") (pin "7") (pinfunction "7_7") (pintype "passive"))
      (node (ref "U5") (pin "88") (pinfunction "P3_0_88") (pintype "bidirectional"))
    )
    (net (code "38") (name "TDI") (class "Default")
      (node (ref "J1") (pin "1") (pinfunction "1_1") (pintype "passive"))
      (node (ref "U5") (pin "91") (pinfunction "P1_10_91") (pintype "bidirectional"))
    )
    (net (code "39") (name "TDO") (class "Default")
      (node (ref "J1") (pin "3") (pinfunction "3_3") (pintype "passive"))
      (node (ref "U5") (pin "90") (pinfunction "P1_9_90") (pintype "bidirectional"))
    )
    (net (code "40") (name "TMS") (class "Default")
      (node (ref "J1") (pin "5") (pinfunction "5_5") (pintype "passive"))
      (node (ref "U5") (pin "89") (pinfunction "P1_8_89") (pintype "bidirectional"))
    )
    (net (code "41") (name "USBHS_FAULT") (class "Default")
      (node (ref "R2") (pin "P$1") (pinfunction "1_P$1") (pintype "passive"))
      (node (ref "U2") (pin "3") (pinfunction "FLG_3") (pintype "input"))
      (node (ref "U5") (pin "78") (pinfunction "P3_8_78") (pintype "bidirectional"))
    )
    (net (code "42") (name "USBHS_N") (class "Default")
      (node (ref "J2") (pin "D-") (pinfunction "D-_D-") (pintype "bidirectional"))
      (node (ref "U5") (pin "31") (pinfunction "USBHS_DM_31") (pintype "bidirectional"))
    )
    (net (code "43") (name "USBHS_P") (class "Default")
      (node (ref "J2") (pin "D+") (pinfunction "D+_D+") (pintype "bidirectional"))
      (node (ref "U5") (pin "32") (pinfunction "USBHS_DP_32") (pintype "bidirectional"))
    )
    (net (code "44") (name "USBHS_VBUS") (class "Default")
      (node (ref "C15") (pin "P$1") (pinfunction "1_P$1") (pintype "passive"))
      (node (ref "C18") (pin "1") (pinfunction "1_1") (pintype "passive"))
      (node (ref "J2") (pin "VBUS") (pinfunction "VBUS_VBUS") (pintype "power_in"))
      (node (ref "U2") (pin "5") (pinfunction "OUT_5") (pintype "input"))
      (node (ref "U5") (pin "17") (pinfunction "PB_1_17") (pintype "bidirectional"))
    )
    (net (code "45") (name "USBHS_VBUSEN") (class "Default")
      (node (ref "R3") (pin "P$1") (pinfunction "1_P$1") (pintype "passive"))
      (node (ref "U2") (pin "1") (pinfunction "EN_1") (pintype "input"))
      (node (ref "U5") (pin "16") (pinfunction "PB_0_16") (pintype "bidirectional"))
    )
    (net (code "46") (name "USB_N") (class "Default")
      (node (ref "R5") (pin "P$1") (pinfunction "1_P$1") (pintype "passive"))
      (node (ref "U5") (pin "46") (pinfunction "USB_DM_46") (pintype "bidirectional"))
    )
    (net (code "47") (name "USB_P") (class "Default")
      (node (ref "R6") (pin "P$1") (pinfunction "1_P$1") (pintype "passive"))
      (node (ref "U5") (pin "47") (pinfunction "USB_DP_47") (pintype "bidirectional"))
    )
    (net (code "48") (name "USB_VBUS_B") (class "Default")
      (node (ref "R4") (pin "P$1") (pinfunction "1_P$1") (pintype "passive"))
      (node (ref "U5") (pin "44") (pinfunction "P4_7_44") (pintype "bidirectional"))
    )
    (net (code "49") (name "VCL_F(FLASH)") (class "Default")
      (node (ref "C21") (pin "P$2") (pinfunction "2_P$2") (pintype "passive"))
      (node (ref "U5") (pin "112") (pinfunction "VCL_F(FLASH)_112") (pintype "bidirectional"))
    )
    (net (code "50") (name "VDD") (class "Default")
      (node (ref "C10") (pin "P$2") (pinfunction "2_P$2") (pintype "passive"))
      (node (ref "C12") (pin "P$2") (pinfunction "2_P$2") (pintype "passive"))
      (node (ref "C13") (pin "P$2") (pinfunction "2_P$2") (pintype "passive"))
      (node (ref "C17") (pin "P$2") (pinfunction "2_P$2") (pintype "passive"))
      (node (ref "C2") (pin "P$1") (pinfunction "1_P$1") (pintype "passive"))
      (node (ref "C22") (pin "P$2") (pinfunction "2_P$2") (pintype "passive"))
      (node (ref "C23") (pin "P$1") (pinfunction "1_P$1") (pintype "passive"))
      (node (ref "C25") (pin "P$2") (pinfunction "2_P$2") (pintype "passive"))
      (node (ref "C26") (pin "P$1") (pinfunction "1_P$1") (pintype "passive"))
      (node (ref "C27") (pin "P$1") (pinfunction "1_P$1") (pintype "passive"))
      (node (ref "C3") (pin "P$1") (pinfunction "1_P$1") (pintype "passive"))
      (node (ref "C30") (pin "P$1") (pinfunction "1_P$1") (pintype "passive"))
      (node (ref "C31") (pin "P$2") (pinfunction "2_P$2") (pintype "passive"))
      (node (ref "C4") (pin "P$1") (pinfunction "1_P$1") (pintype "passive"))
      (node (ref "C6") (pin "P$2") (pinfunction "2_P$2") (pintype "passive"))
      (node (ref "J1") (pin "2") (pinfunction "2_2") (pintype "passive"))
      (node (ref "J1") (pin "4") (pinfunction "4_4") (pintype "passive"))
      (node (ref "L1") (pin "2") (pinfunction "P$2_2") (pintype "bidirectional"))
      (node (ref "R1") (pin "P$2") (pinfunction "2_P$2") (pintype "passive"))
      (node (ref "R10") (pin "P$2") (pinfunction "2_P$2") (pintype "passive"))
      (node (ref "U1") (pin "P3") (pinfunction "VDD1_P3") (pintype "bidirectional"))
      (node (ref "U1") (pin "P4") (pinfunction "VDD_P4") (pintype "bidirectional"))
      (node (ref "U5") (pin "110") (pinfunction "VCC(IO)5_110") (pintype "bidirectional"))
      (node (ref "U5") (pin "123") (pinfunction "VCC(IO)6_123") (pintype "bidirectional"))
      (node (ref "U5") (pin "138") (pinfunction "VCC(IO)7_138") (pintype "bidirectional"))
      (node (ref "U5") (pin "149") (pinfunction "VCC(IO)8_149") (pintype "bidirectional"))
      (node (ref "U5") (pin "155") (pinfunction "AVCC0_155") (pintype "bidirectional"))
      (node (ref "U5") (pin "171") (pinfunction "VCC(IO)9_171") (pintype "bidirectional"))
      (node (ref "U5") (pin "25") (pinfunction "VCC1_25") (pintype "bidirectional"))
      (node (ref "U5") (pin "26") (pinfunction "AVCC_SUBHS_26") (pintype "bidirectional"))
      (node (ref "U5") (pin "34") (pinfunction "VCC_USBHS_34") (pintype "bidirectional"))
      (node (ref "U5") (pin "48") (pinfunction "VCC_USB_48") (pintype "bidirectional"))
      (node (ref "U5") (pin "61") (pinfunction "VCC(IO)2_61") (pintype "bidirectional"))
      (node (ref "U5") (pin "84") (pinfunction "VCC(IO)3_84") (pintype "bidirectional"))
      (node (ref "U5") (pin "97") (pinfunction "VCC(IO)4_97") (pintype "bidirectional"))
    )
    (net (code "51") (name "VDD5") (class "Default")
      (node (ref "C11") (pin "P$1") (pinfunction "1_P$1") (pintype "passive"))
      (node (ref "C8") (pin "P$1") (pinfunction "1_P$1") (pintype "passive"))
      (node (ref "J3") (pin "P$4") (pinfunction "P$4_P$4") (pintype "bidirectional"))
      (node (ref "R2") (pin "P$2") (pinfunction "2_P$2") (pintype "passive"))
      (node (ref "R3") (pin "P$2") (pinfunction "2_P$2") (pintype "passive"))
      (node (ref "U2") (pin "4") (pinfunction "VIN_4") (pintype "input"))
    )
    (net (code "52") (name "VDDIN") (class "Default")
      (node (ref "J3") (pin "P$2") (pinfunction "P$2_P$2") (pintype "bidirectional"))
      (node (ref "L1") (pin "1") (pinfunction "P$1_1") (pintype "bidirectional"))
    )
    (net (code "53") (name "XCIN") (class "Default")
      (node (ref "C19") (pin "P$1") (pinfunction "1_P$1") (pintype "passive"))
      (node (ref "U5") (pin "20") (pinfunction "XCIN_20") (pintype "bidirectional"))
      (node (ref "X2") (pin "P$1") (pinfunction "P$1_P$1") (pintype "bidirectional"))
    )
    (net (code "54") (name "XCOUT") (class "Default")
      (node (ref "C24") (pin "P$1") (pinfunction "1_P$1") (pintype "passive"))
      (node (ref "U5") (pin "21") (pinfunction "XCOUT_21") (pintype "bidirectional"))
      (node (ref "X2") (pin "P$2") (pinfunction "P$2_P$2") (pintype "bidirectional"))
    )
    (net (code "55") (name "XTAL1") (class "Default")
      (node (ref "C7") (pin "P$1") (pinfunction "1_P$1") (pintype "passive"))
      (node (ref "U5") (pin "23") (pinfunction "P2_13/XTAL_23") (pintype "bidirectional"))
      (node (ref "X1") (pin "1") (pinfunction "1_1") (pintype "bidirectional"))
    )
    (net (code "56") (name "XTAL2") (class "Default")
      (node (ref "C14") (pin "P$1") (pinfunction "1_P$1") (pintype "passive"))
      (node (ref "U5") (pin "24") (pinfunction "P2_12/EXTAL_24") (pintype "bidirectional"))
      (node (ref "X1") (pin "3") (pinfunction "3_3") (pintype "bidirectional"))
    )
    (net (code "57") (name "X_DIR") (class "Default")
      (node (ref "J4") (pin "P$3") (pinfunction "P$3_P$3") (pintype "bidirectional"))
      (node (ref "U5") (pin "118") (pinfunction "P6_4_118") (pintype "bidirectional"))
    )
    (net (code "58") (name "X_LS") (class "Default")
      (node (ref "J4") (pin "P$2") (pinfunction "P$2_P$2") (pintype "bidirectional"))
      (node (ref "U5") (pin "164") (pinfunction "P0_5/AN101_164") (pintype "bidirectional"))
    )
    (net (code "59") (name "X_STEP") (class "Default")
      (node (ref "J4") (pin "P$11") (pinfunction "P$11_P$11") (pintype "bidirectional"))
      (node (ref "U5") (pin "86") (pinfunction "P3_2_86") (pintype "bidirectional"))
    )
    (net (code "60") (name "Y_DIR") (class "Default")
      (node (ref "J4") (pin "P$5") (pinfunction "P$5_P$5") (pintype "bidirectional"))
      (node (ref "U5") (pin "115") (pinfunction "P6_7_115") (pintype "bidirectional"))
    )
    (net (code "61") (name "Y_LS") (class "Default")
      (node (ref "J4") (pin "P$4") (pinfunction "P$4_P$4") (pintype "bidirectional"))
      (node (ref "U5") (pin "175") (pinfunction "P5_12_175") (pintype "bidirectional"))
    )
    (net (code "62") (name "Y_STEP") (class "Default")
      (node (ref "J4") (pin "P$13") (pinfunction "P$13_P$13") (pintype "bidirectional"))
      (node (ref "U5") (pin "82") (pinfunction "P3_4_82") (pintype "bidirectional"))
    )
    (net (code "63") (name "Z_DIR") (class "Default")
      (node (ref "J4") (pin "P$1") (pinfunction "P$1_P$1") (pintype "bidirectional"))
      (node (ref "U5") (pin "121") (pinfunction "P6_1_121") (pintype "bidirectional"))
    )
    (net (code "64") (name "Z_LS") (class "Default")
      (node (ref "J4") (pin "P$6") (pinfunction "P$6_P$6") (pintype "bidirectional"))
      (node (ref "U5") (pin "169") (pinfunction "P0_0/AN0\\00_169") (pintype "bidirectional"))
    )
    (net (code "65") (name "Z_STEP") (class "Default")
      (node (ref "J4") (pin "P$9") (pinfunction "P$9_P$9") (pintype "bidirectional"))
      (node (ref "U5") (pin "92") (pinfunction "P1_11_92") (pintype "bidirectional"))
    )
    (net (code "66") (name "unconnected-(U5-P0_1{slash}AN001-Pad168)") (class "Default")
      (node (ref "U5") (pin "168") (pinfunction "P0_1/AN001_168") (pintype "bidirectional"))
    )
    (net (code "67") (name "unconnected-(U5-P0_2{slash}AN002-Pad167)") (class "Default")
      (node (ref "U5") (pin "167") (pinfunction "P0_2/AN002_167") (pintype "bidirectional"))
    )
    (net (code "68") (name "unconnected-(U5-P0_3{slash}PGAVSS000-Pad166)") (class "Default")
      (node (ref "U5") (pin "166") (pinfunction "P0_3/PGAVSS000_166") (pintype "bidirectional"))
    )
    (net (code "69") (name "unconnected-(U5-P0_4{slash}AN100-Pad165)") (class "Default")
      (node (ref "U5") (pin "165") (pinfunction "P0_4/AN100_165") (pintype "bidirectional"))
    )
    (net (code "70") (name "unconnected-(U5-P0_6{slash}AN102-Pad163)") (class "Default")
      (node (ref "U5") (pin "163") (pinfunction "P0_6/AN102_163") (pintype "bidirectional"))
    )
    (net (code "71") (name "unconnected-(U5-P0_7{slash}PGVSS100-Pad162)") (class "Default")
      (node (ref "U5") (pin "162") (pinfunction "P0_7/PGVSS100_162") (pintype "bidirectional"))
    )
    (net (code "72") (name "unconnected-(U5-P0_8{slash}AN003-Pad161)") (class "Default")
      (node (ref "U5") (pin "161") (pinfunction "P0_8/AN003_161") (pintype "bidirectional"))
    )
    (net (code "73") (name "unconnected-(U5-P0_9{slash}AN004-Pad160)") (class "Default")
      (node (ref "U5") (pin "160") (pinfunction "P0_9/AN004_160") (pintype "bidirectional"))
    )
    (net (code "74") (name "unconnected-(U5-P0_14{slash}DA0{slash}AN005{slash}AN105-Pad152)") (class "Default")
      (node (ref "U5") (pin "152") (pinfunction "P0_14/DA0/AN005/AN105_152") (pintype "bidirectional"))
    )
    (net (code "75") (name "unconnected-(U5-P0_15{slash}DA1{slash}AN006{slash}AN106-Pad151)") (class "Default")
      (node (ref "U5") (pin "151") (pinfunction "P0_15/DA1/AN006/AN106_151") (pintype "bidirectional"))
    )
    (net (code "76") (name "unconnected-(U5-P1_0-Pad132)") (class "Default")
      (node (ref "U5") (pin "132") (pinfunction "P1_0_132") (pintype "bidirectional"))
    )
    (net (code "77") (name "unconnected-(U5-P1_1-Pad131)") (class "Default")
      (node (ref "U5") (pin "131") (pinfunction "P1_1_131") (pintype "bidirectional"))
    )
    (net (code "78") (name "unconnected-(U5-P1_2-Pad130)") (class "Default")
      (node (ref "U5") (pin "130") (pinfunction "P1_2_130") (pintype "bidirectional"))
    )
    (net (code "79") (name "unconnected-(U5-P1_3-Pad129)") (class "Default")
      (node (ref "U5") (pin "129") (pinfunction "P1_3_129") (pintype "bidirectional"))
    )
    (net (code "80") (name "unconnected-(U5-P1_4-Pad128)") (class "Default")
      (node (ref "U5") (pin "128") (pinfunction "P1_4_128") (pintype "bidirectional"))
    )
    (net (code "81") (name "unconnected-(U5-P1_5-Pad127)") (class "Default")
      (node (ref "U5") (pin "127") (pinfunction "P1_5_127") (pintype "bidirectional"))
    )
    (net (code "82") (name "unconnected-(U5-P1_6-Pad126)") (class "Default")
      (node (ref "U5") (pin "126") (pinfunction "P1_6_126") (pintype "bidirectional"))
    )
    (net (code "83") (name "unconnected-(U5-P1_7-Pad125)") (class "Default")
      (node (ref "U5") (pin "125") (pinfunction "P1_7_125") (pintype "bidirectional"))
    )
    (net (code "84") (name "unconnected-(U5-P1_12-Pad93)") (class "Default")
      (node (ref "U5") (pin "93") (pinfunction "P1_12_93") (pintype "bidirectional"))
    )
    (net (code "85") (name "unconnected-(U5-P1_13-Pad94)") (class "Default")
      (node (ref "U5") (pin "94") (pinfunction "P1_13_94") (pintype "bidirectional"))
    )
    (net (code "86") (name "unconnected-(U5-P1_14-Pad95)") (class "Default")
      (node (ref "U5") (pin "95") (pinfunction "P1_14_95") (pintype "bidirectional"))
    )
    (net (code "87") (name "unconnected-(U5-P1_15-Pad96)") (class "Default")
      (node (ref "U5") (pin "96") (pinfunction "P1_15_96") (pintype "bidirectional"))
    )
    (net (code "88") (name "unconnected-(U5-P2_0(INPUT_ONLY)-Pad69)") (class "Default")
      (node (ref "U5") (pin "69") (pinfunction "P2_0(INPUT_ONLY)_69") (pintype "bidirectional"))
    )
    (net (code "89") (name "unconnected-(U5-P2_7-Pad49)") (class "Default")
      (node (ref "U5") (pin "49") (pinfunction "P2_7_49") (pintype "bidirectional"))
    )
    (net (code "90") (name "unconnected-(U5-P3_1-Pad87)") (class "Default")
      (node (ref "U5") (pin "87") (pinfunction "P3_1_87") (pintype "bidirectional"))
    )
    (net (code "91") (name "unconnected-(U5-P3_3-Pad85)") (class "Default")
      (node (ref "U5") (pin "85") (pinfunction "P3_3_85") (pintype "bidirectional"))
    )
    (net (code "92") (name "unconnected-(U5-P3_5-Pad81)") (class "Default")
      (node (ref "U5") (pin "81") (pinfunction "P3_5_81") (pintype "bidirectional"))
    )
    (net (code "93") (name "unconnected-(U5-P3_6-Pad80)") (class "Default")
      (node (ref "U5") (pin "80") (pinfunction "P3_6_80") (pintype "bidirectional"))
    )
    (net (code "94") (name "unconnected-(U5-P3_7-Pad79)") (class "Default")
      (node (ref "U5") (pin "79") (pinfunction "P3_7_79") (pintype "bidirectional"))
    )
    (net (code "95") (name "unconnected-(U5-P3_9-Pad77)") (class "Default")
      (node (ref "U5") (pin "77") (pinfunction "P3_9_77") (pintype "bidirectional"))
    )
    (net (code "96") (name "unconnected-(U5-P3_10-Pad76)") (class "Default")
      (node (ref "U5") (pin "76") (pinfunction "P3_10_76") (pintype "bidirectional"))
    )
    (net (code "97") (name "unconnected-(U5-P3_11-Pad75)") (class "Default")
      (node (ref "U5") (pin "75") (pinfunction "P3_11_75") (pintype "bidirectional"))
    )
    (net (code "98") (name "unconnected-(U5-P3_12-Pad74)") (class "Default")
      (node (ref "U5") (pin "74") (pinfunction "P3_12_74") (pintype "bidirectional"))
    )
    (net (code "99") (name "unconnected-(U5-P3_13-Pad55)") (class "Default")
      (node (ref "U5") (pin "55") (pinfunction "P3_13_55") (pintype "bidirectional"))
    )
    (net (code "100") (name "unconnected-(U5-P3_14-Pad56)") (class "Default")
      (node (ref "U5") (pin "56") (pinfunction "P3_14_56") (pintype "bidirectional"))
    )
    (net (code "101") (name "unconnected-(U5-P3_15-Pad57)") (class "Default")
      (node (ref "U5") (pin "57") (pinfunction "P3_15_57") (pintype "bidirectional"))
    )
    (net (code "102") (name "unconnected-(U5-P4_0-Pad1)") (class "Default")
      (node (ref "U5") (pin "1") (pinfunction "P4_0_1") (pintype "bidirectional"))
    )
    (net (code "103") (name "unconnected-(U5-P4_1-Pad2)") (class "Default")
      (node (ref "U5") (pin "2") (pinfunction "P4_1_2") (pintype "bidirectional"))
    )
    (net (code "104") (name "unconnected-(U5-P4_2-Pad3)") (class "Default")
      (node (ref "U5") (pin "3") (pinfunction "P4_2_3") (pintype "bidirectional"))
    )
    (net (code "105") (name "unconnected-(U5-P4_8-Pad43)") (class "Default")
      (node (ref "U5") (pin "43") (pinfunction "P4_8_43") (pintype "bidirectional"))
    )
    (net (code "106") (name "unconnected-(U5-P4_10-Pad41)") (class "Default")
      (node (ref "U5") (pin "41") (pinfunction "P4_10_41") (pintype "bidirectional"))
    )
    (net (code "107") (name "unconnected-(U5-P4_11-Pad40)") (class "Default")
      (node (ref "U5") (pin "40") (pinfunction "P4_11_40") (pintype "bidirectional"))
    )
    (net (code "108") (name "unconnected-(U5-P4_12-Pad39)") (class "Default")
      (node (ref "U5") (pin "39") (pinfunction "P4_12_39") (pintype "bidirectional"))
    )
    (net (code "109") (name "unconnected-(U5-P4_13-Pad38)") (class "Default")
      (node (ref "U5") (pin "38") (pinfunction "P4_13_38") (pintype "bidirectional"))
    )
    (net (code "110") (name "unconnected-(U5-P4_14-Pad37)") (class "Default")
      (node (ref "U5") (pin "37") (pinfunction "P4_14_37") (pintype "bidirectional"))
    )
    (net (code "111") (name "unconnected-(U5-P4_15-Pad36)") (class "Default")
      (node (ref "U5") (pin "36") (pinfunction "P4_15_36") (pintype "bidirectional"))
    )
    (net (code "112") (name "unconnected-(U5-P5_0{slash}AN016-Pad140)") (class "Default")
      (node (ref "U5") (pin "140") (pinfunction "P5_0/AN016_140") (pintype "bidirectional"))
    )
    (net (code "113") (name "unconnected-(U5-P5_1{slash}AN116-Pad141)") (class "Default")
      (node (ref "U5") (pin "141") (pinfunction "P5_1/AN116_141") (pintype "bidirectional"))
    )
    (net (code "114") (name "unconnected-(U5-P5_2{slash}AN017-Pad142)") (class "Default")
      (node (ref "U5") (pin "142") (pinfunction "P5_2/AN017_142") (pintype "bidirectional"))
    )
    (net (code "115") (name "unconnected-(U5-P5_3{slash}AN117-Pad143)") (class "Default")
      (node (ref "U5") (pin "143") (pinfunction "P5_3/AN117_143") (pintype "bidirectional"))
    )
    (net (code "116") (name "unconnected-(U5-P5_4{slash}AN018-Pad144)") (class "Default")
      (node (ref "U5") (pin "144") (pinfunction "P5_4/AN018_144") (pintype "bidirectional"))
    )
    (net (code "117") (name "unconnected-(U5-P5_5{slash}AN118-Pad145)") (class "Default")
      (node (ref "U5") (pin "145") (pinfunction "P5_5/AN118_145") (pintype "bidirectional"))
    )
    (net (code "118") (name "unconnected-(U5-P5_6{slash}AN019-Pad146)") (class "Default")
      (node (ref "U5") (pin "146") (pinfunction "P5_6/AN019_146") (pintype "bidirectional"))
    )
    (net (code "119") (name "unconnected-(U5-P5_7{slash}AN119-Pad147)") (class "Default")
      (node (ref "U5") (pin "147") (pinfunction "P5_7/AN119_147") (pintype "bidirectional"))
    )
    (net (code "120") (name "unconnected-(U5-P5_11-Pad176)") (class "Default")
      (node (ref "U5") (pin "176") (pinfunction "P5_11_176") (pintype "bidirectional"))
    )
    (net (code "121") (name "unconnected-(U5-P5_13-Pad174)") (class "Default")
      (node (ref "U5") (pin "174") (pinfunction "P5_13_174") (pintype "bidirectional"))
    )
    (net (code "122") (name "unconnected-(U5-P6_0-Pad122)") (class "Default")
      (node (ref "U5") (pin "122") (pinfunction "P6_0_122") (pintype "bidirectional"))
    )
    (net (code "123") (name "unconnected-(U5-P6_2-Pad120)") (class "Default")
      (node (ref "U5") (pin "120") (pinfunction "P6_2_120") (pintype "bidirectional"))
    )
    (net (code "124") (name "unconnected-(U5-P6_3-Pad119)") (class "Default")
      (node (ref "U5") (pin "119") (pinfunction "P6_3_119") (pintype "bidirectional"))
    )
    (net (code "125") (name "unconnected-(U5-P6_5-Pad117)") (class "Default")
      (node (ref "U5") (pin "117") (pinfunction "P6_5_117") (pintype "bidirectional"))
    )
    (net (code "126") (name "unconnected-(U5-P6_6-Pad116)") (class "Default")
      (node (ref "U5") (pin "116") (pinfunction "P6_6_116") (pintype "bidirectional"))
    )
    (net (code "127") (name "unconnected-(U5-P6_8-Pad99)") (class "Default")
      (node (ref "U5") (pin "99") (pinfunction "P6_8_99") (pintype "bidirectional"))
    )
    (net (code "128") (name "unconnected-(U5-P6_9-Pad100)") (class "Default")
      (node (ref "U5") (pin "100") (pinfunction "P6_9_100") (pintype "bidirectional"))
    )
    (net (code "129") (name "unconnected-(U5-P6_11-Pad102)") (class "Default")
      (node (ref "U5") (pin "102") (pinfunction "P6_11_102") (pintype "bidirectional"))
    )
    (net (code "130") (name "unconnected-(U5-P6_12-Pad103)") (class "Default")
      (node (ref "U5") (pin "103") (pinfunction "P6_12_103") (pintype "bidirectional"))
    )
    (net (code "131") (name "unconnected-(U5-P6_13-Pad104)") (class "Default")
      (node (ref "U5") (pin "104") (pinfunction "P6_13_104") (pintype "bidirectional"))
    )
    (net (code "132") (name "unconnected-(U5-P6_14-Pad105)") (class "Default")
      (node (ref "U5") (pin "105") (pinfunction "P6_14_105") (pintype "bidirectional"))
    )
    (net (code "133") (name "unconnected-(U5-P6_15-Pad106)") (class "Default")
      (node (ref "U5") (pin "106") (pinfunction "P6_15_106") (pintype "bidirectional"))
    )
    (net (code "134") (name "unconnected-(U5-P7_6-Pad14)") (class "Default")
      (node (ref "U5") (pin "14") (pinfunction "P7_6_14") (pintype "bidirectional"))
    )
    (net (code "135") (name "unconnected-(U5-P7_7-Pad15)") (class "Default")
      (node (ref "U5") (pin "15") (pinfunction "P7_7_15") (pintype "bidirectional"))
    )
    (net (code "136") (name "unconnected-(U5-P8_0-Pad133)") (class "Default")
      (node (ref "U5") (pin "133") (pinfunction "P8_0_133") (pintype "bidirectional"))
    )
    (net (code "137") (name "unconnected-(U5-P8_1-Pad134)") (class "Default")
      (node (ref "U5") (pin "134") (pinfunction "P8_1_134") (pintype "bidirectional"))
    )
    (net (code "138") (name "unconnected-(U5-P8_2-Pad135)") (class "Default")
      (node (ref "U5") (pin "135") (pinfunction "P8_2_135") (pintype "bidirectional"))
    )
    (net (code "139") (name "unconnected-(U5-P8_3-Pad136)") (class "Default")
      (node (ref "U5") (pin "136") (pinfunction "P8_3_136") (pintype "bidirectional"))
    )
    (net (code "140") (name "unconnected-(U5-P8_4-Pad137)") (class "Default")
      (node (ref "U5") (pin "137") (pinfunction "P8_4_137") (pintype "bidirectional"))
    )
    (net (code "141") (name "unconnected-(U5-P8_5-Pad173)") (class "Default")
      (node (ref "U5") (pin "173") (pinfunction "P8_5_173") (pintype "bidirectional"))
    )
    (net (code "142") (name "unconnected-(U5-P9_0-Pad58)") (class "Default")
      (node (ref "U5") (pin "58") (pinfunction "P9_0_58") (pintype "bidirectional"))
    )
    (net (code "143") (name "unconnected-(U5-P9_1-Pad59)") (class "Default")
      (node (ref "U5") (pin "59") (pinfunction "P9_1_59") (pintype "bidirectional"))
    )
    (net (code "144") (name "unconnected-(U5-P9_5-Pad73)") (class "Default")
      (node (ref "U5") (pin "73") (pinfunction "P9_5_73") (pintype "bidirectional"))
    )
    (net (code "145") (name "unconnected-(U5-P9_6-Pad72)") (class "Default")
      (node (ref "U5") (pin "72") (pinfunction "P9_6_72") (pintype "bidirectional"))
    )
    (net (code "146") (name "unconnected-(U5-P9_7-Pad71)") (class "Default")
      (node (ref "U5") (pin "71") (pinfunction "P9_7_71") (pintype "bidirectional"))
    )
    (net (code "147") (name "unconnected-(U5-P9_8-Pad70)") (class "Default")
      (node (ref "U5") (pin "70") (pinfunction "P9_8_70") (pintype "bidirectional"))
    )
    (net (code "148") (name "unconnected-(U5-PA_0-Pad114)") (class "Default")
      (node (ref "U5") (pin "114") (pinfunction "PA_0_114") (pintype "bidirectional"))
    )
    (net (code "149") (name "unconnected-(U5-PA_1-Pad113)") (class "Default")
      (node (ref "U5") (pin "113") (pinfunction "PA_1_113") (pintype "bidirectional"))
    )
    (net (code "150") (name "unconnected-(U5-PA_8-Pad107)") (class "Default")
      (node (ref "U5") (pin "107") (pinfunction "PA_8_107") (pintype "bidirectional"))
    )
    (net (code "151") (name "unconnected-(U5-PA_9-Pad108)") (class "Default")
      (node (ref "U5") (pin "108") (pinfunction "PA_9_108") (pintype "bidirectional"))
    )
    (net (code "152") (name "unconnected-(U5-PA_10-Pad109)") (class "Default")
      (node (ref "U5") (pin "109") (pinfunction "PA_10_109") (pintype "bidirectional"))
    )
    (net (code "153") (name "unconnected-(U5-VBAT-Pad18)") (class "Default")
      (node (ref "U5") (pin "18") (pinfunction "VBAT_18") (pintype "bidirectional"))
    )
    (net (code "154") (name "unconnected-(U5-VREFH-Pad154)") (class "Default")
      (node (ref "U5") (pin "154") (pinfunction "VREFH_154") (pintype "bidirectional"))
    )
    (net (code "155") (name "unconnected-(U5-VREFH0-Pad158)") (class "Default")
      (node (ref "U5") (pin "158") (pinfunction "VREFH0_158") (pintype "bidirectional"))
    )
    (net (code "156") (name "unconnected-(U5-VREFL-Pad153)") (class "Default")
      (node (ref "U5") (pin "153") (pinfunction "VREFL_153") (pintype "bidirectional"))
    )
    (net (code "157") (name "unconnected-(U5-VREFL0-Pad157)") (class "Default")
      (node (ref "U5") (pin "157") (pinfunction "VREFL0_157") (pintype "bidirectional"))
    )
  )
)
